# CallerID_V12.net
KiCad netlist of a schematic drawn in EAGLE
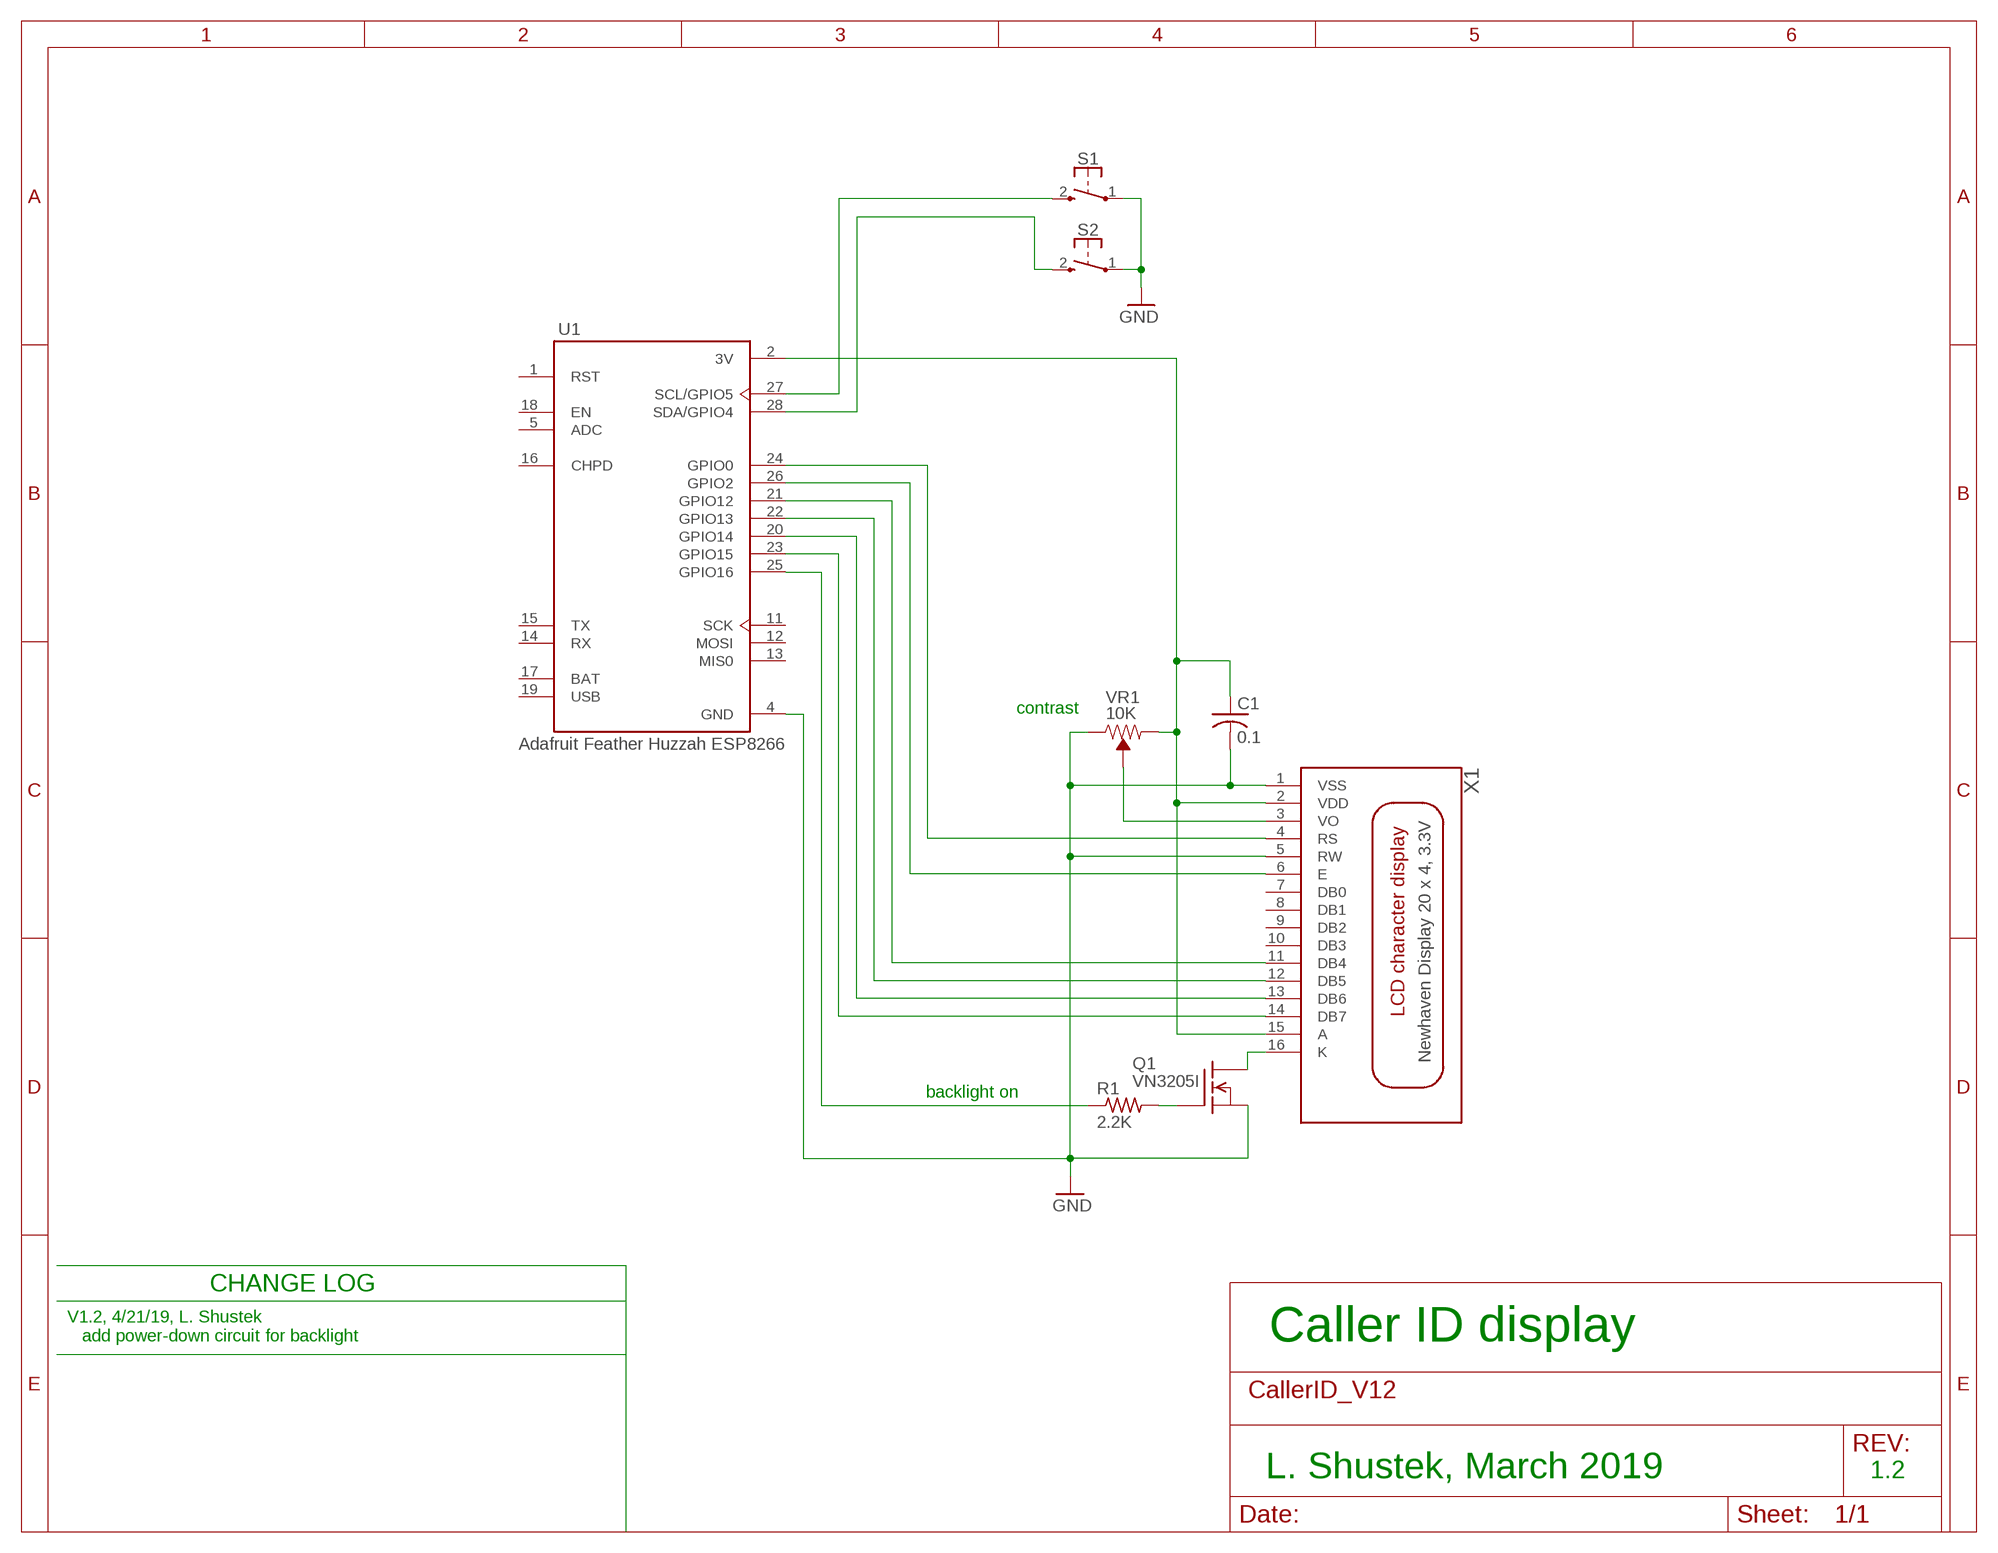
[diagram p0: schematic, sheet 1]

(export (version "E")
  (design (tool "Eeschema 10.0.6"))
  (components
    (comp (ref "C1")
      (value "0.1")
      (footprint "eagle-import:C050-024X044")
      (libsource (lib "eagle-import") (part "C-US050-024X044"))
    )
    (comp (ref "Q1")
      (value "VN3205I")
      (footprint "eagle-import:TO92-INLINE")
      (libsource (lib "eagle-import") (part "VN3205I"))
    )
    (comp (ref "R1")
      (value "2.2K")
      (footprint "eagle-import:0207_10")
      (libsource (lib "eagle-import") (part "R-US_0207/10"))
    )
    (comp (ref "S1")
      (value "PUSHBUTTON-SPST")
      (footprint "eagle-import:PUSHBUTTON-SPST")
      (libsource (lib "eagle-import") (part "PUSHBUTTON-SPST"))
    )
    (comp (ref "S2")
      (value "PUSHBUTTON-SPST")
      (footprint "eagle-import:PUSHBUTTON-SPST")
      (libsource (lib "eagle-import") (part "PUSHBUTTON-SPST"))
    )
    (comp (ref "U1")
      (value "Adafruit Feather Huzzah ESP8266")
      (footprint "eagle-import:ADAFRUIT-FEATHER-WIFI")
      (fields (field (name "MF") "Adafruit Industries") (field (name "MP") "2821"))
      (libsource (lib "eagle-import") (part "ADAFRUIT-FEATHER-WIFI"))
    )
    (comp (ref "VR1")
      (value "10K")
      (footprint "eagle-import:TRIMBOT-BOURNS-3362M")
      (libsource (lib "eagle-import") (part "TRIMPOT"))
    )
    (comp (ref "X1")
      (value "Newhaven Display 20 x 4, 3.3V")
      (footprint "eagle-import:LCD-CHARACTER-DISPLAY-20X4-NEWHAVEN")
      (libsource (lib "eagle-import") (part "LCD-CHARACTER-DISPLAYLCD-CHARACTER-DISPLAY-20X4-NEWHAVEN"))
    )
  )
  (nets
    (net (code "1") (name "GND") (class "Default")
      (node (ref "C1") (pin "2") (pinfunction "2_2") (pintype "passive"))
      (node (ref "Q1") (pin "1") (pinfunction "S_1") (pintype "passive"))
      (node (ref "S1") (pin "1") (pinfunction "1_1") (pintype "passive"))
      (node (ref "S2") (pin "1") (pinfunction "1_1") (pintype "passive"))
      (node (ref "U1") (pin "4") (pinfunction "GND_4") (pintype "power_in"))
      (node (ref "VR1") (pin "3") (pinfunction "CW_3") (pintype "passive"))
      (node (ref "X1") (pin "1") (pinfunction "VSS_1") (pintype "power_in"))
      (node (ref "X1") (pin "5") (pinfunction "RW_5") (pintype "input"))
    )
    (net (code "2") (name "Net-(Q1-D)") (class "Default")
      (node (ref "Q1") (pin "3") (pinfunction "D_3") (pintype "passive"))
      (node (ref "X1") (pin "16") (pinfunction "K_16") (pintype "input"))
    )
    (net (code "3") (name "Net-(Q1-G)") (class "Default")
      (node (ref "Q1") (pin "2") (pinfunction "G_2") (pintype "passive"))
      (node (ref "R1") (pin "2") (pinfunction "2_2") (pintype "passive"))
    )
    (net (code "4") (name "Net-(S1-3)") (class "Default")
      (node (ref "S1") (pin "2") (pinfunction "3_2") (pintype "passive"))
      (node (ref "U1") (pin "27") (pinfunction "SCL/GPIO5_27") (pintype "bidirectional"))
    )
    (net (code "5") (name "Net-(S2-3)") (class "Default")
      (node (ref "S2") (pin "2") (pinfunction "3_2") (pintype "passive"))
      (node (ref "U1") (pin "28") (pinfunction "SDA/GPIO4_28") (pintype "bidirectional"))
    )
    (net (code "6") (name "Net-(U1-3V)") (class "Default")
      (node (ref "C1") (pin "1") (pinfunction "1_1") (pintype "passive"))
      (node (ref "U1") (pin "2") (pinfunction "3V_2") (pintype "power_in"))
      (node (ref "VR1") (pin "1") (pinfunction "CCW_1") (pintype "passive"))
      (node (ref "X1") (pin "15") (pinfunction "A_15") (pintype "input"))
      (node (ref "X1") (pin "2") (pinfunction "VDD_2") (pintype "power_in"))
    )
    (net (code "7") (name "Net-(U1-GPIO0)") (class "Default")
      (node (ref "U1") (pin "24") (pinfunction "GPIO0_24") (pintype "bidirectional"))
      (node (ref "X1") (pin "4") (pinfunction "RS_4") (pintype "input"))
    )
    (net (code "8") (name "Net-(U1-GPIO2)") (class "Default")
      (node (ref "U1") (pin "26") (pinfunction "GPIO2_26") (pintype "bidirectional"))
      (node (ref "X1") (pin "6") (pinfunction "E_6") (pintype "input"))
    )
    (net (code "9") (name "Net-(U1-GPIO12)") (class "Default")
      (node (ref "U1") (pin "21") (pinfunction "GPIO12_21") (pintype "bidirectional"))
      (node (ref "X1") (pin "11") (pinfunction "DB4_11") (pintype "bidirectional"))
    )
    (net (code "10") (name "Net-(U1-GPIO13)") (class "Default")
      (node (ref "U1") (pin "22") (pinfunction "GPIO13_22") (pintype "bidirectional"))
      (node (ref "X1") (pin "12") (pinfunction "DB5_12") (pintype "bidirectional"))
    )
    (net (code "11") (name "Net-(U1-GPIO14)") (class "Default")
      (node (ref "U1") (pin "20") (pinfunction "GPIO14_20") (pintype "bidirectional"))
      (node (ref "X1") (pin "13") (pinfunction "DB6_13") (pintype "bidirectional"))
    )
    (net (code "12") (name "Net-(U1-GPIO15)") (class "Default")
      (node (ref "U1") (pin "23") (pinfunction "GPIO15_23") (pintype "bidirectional"))
      (node (ref "X1") (pin "14") (pinfunction "DB7_14") (pintype "bidirectional"))
    )
    (net (code "13") (name "Net-(U1-GPIO16)") (class "Default")
      (node (ref "R1") (pin "1") (pinfunction "1_1") (pintype "passive"))
      (node (ref "U1") (pin "25") (pinfunction "GPIO16_25") (pintype "bidirectional"))
    )
    (net (code "14") (name "Net-(VR1-WIPER)") (class "Default")
      (node (ref "VR1") (pin "2") (pinfunction "WIPER_2") (pintype "passive"))
      (node (ref "X1") (pin "3") (pinfunction "VO_3") (pintype "input"))
    )
    (net (code "15") (name "unconnected-(U1-ADC-Pad5)") (class "Default")
      (node (ref "U1") (pin "5") (pinfunction "ADC_5") (pintype "bidirectional"))
    )
    (net (code "16") (name "unconnected-(U1-BAT-Pad17)") (class "Default")
      (node (ref "U1") (pin "17") (pinfunction "BAT_17") (pintype "bidirectional"))
    )
    (net (code "17") (name "unconnected-(U1-CHPD-Pad16)") (class "Default")
      (node (ref "U1") (pin "16") (pinfunction "CHPD_16") (pintype "bidirectional"))
    )
    (net (code "18") (name "unconnected-(U1-EN-Pad18)") (class "Default")
      (node (ref "U1") (pin "18") (pinfunction "EN_18") (pintype "input"))
    )
    (net (code "19") (name "unconnected-(U1-MIS0-Pad13)") (class "Default")
      (node (ref "U1") (pin "13") (pinfunction "MIS0_13") (pintype "input"))
    )
    (net (code "20") (name "unconnected-(U1-MOSI-Pad12)") (class "Default")
      (node (ref "U1") (pin "12") (pinfunction "MOSI_12") (pintype "output"))
    )
    (net (code "21") (name "unconnected-(U1-RST-Pad1)") (class "Default")
      (node (ref "U1") (pin "1") (pinfunction "RST_1") (pintype "input"))
    )
    (net (code "22") (name "unconnected-(U1-RX-Pad14)") (class "Default")
      (node (ref "U1") (pin "14") (pinfunction "RX_14") (pintype "input"))
    )
    (net (code "23") (name "unconnected-(U1-SCK-Pad11)") (class "Default")
      (node (ref "U1") (pin "11") (pinfunction "SCK_11") (pintype "bidirectional"))
    )
    (net (code "24") (name "unconnected-(U1-TX-Pad15)") (class "Default")
      (node (ref "U1") (pin "15") (pinfunction "TX_15") (pintype "output"))
    )
    (net (code "25") (name "unconnected-(U1-USB-Pad19)") (class "Default")
      (node (ref "U1") (pin "19") (pinfunction "USB_19") (pintype "bidirectional"))
    )
    (net (code "26") (name "unconnected-(X1-DB0-Pad7)") (class "Default")
      (node (ref "X1") (pin "7") (pinfunction "DB0_7") (pintype "bidirectional"))
    )
    (net (code "27") (name "unconnected-(X1-DB1-Pad8)") (class "Default")
      (node (ref "X1") (pin "8") (pinfunction "DB1_8") (pintype "bidirectional"))
    )
    (net (code "28") (name "unconnected-(X1-DB2-Pad9)") (class "Default")
      (node (ref "X1") (pin "9") (pinfunction "DB2_9") (pintype "bidirectional"))
    )
    (net (code "29") (name "unconnected-(X1-DB3-Pad10)") (class "Default")
      (node (ref "X1") (pin "10") (pinfunction "DB3_10") (pintype "bidirectional"))
    )
  )
)
